# MotherBoardV1.net
KiCad netlist of a schematic drawn in EAGLE
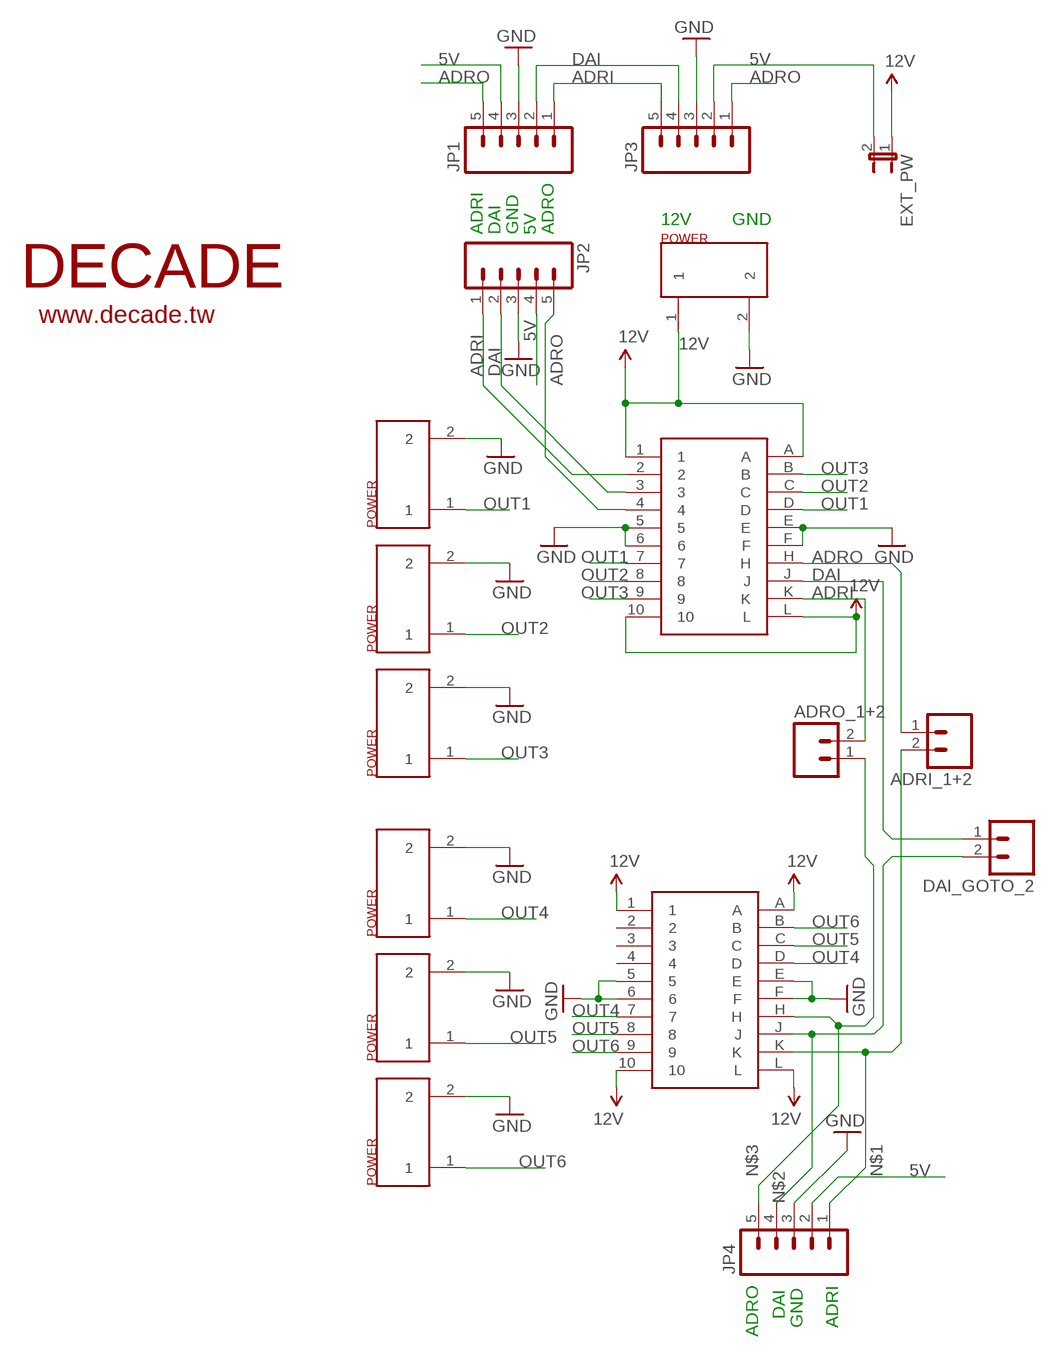
[diagram p0: schematic, sheet 1]

(export (version "E")
  (design (tool "Eeschema 10.0.6"))
  (components
    (comp (ref "ADRI_1+2")
      (value "M02LOCK")
      (footprint "eagle-import:1X02_LOCK")
      (libsource (lib "eagle-import") (part "M02LOCK"))
    )
    (comp (ref "ADRO_1+2")
      (value "M02LOCK")
      (footprint "eagle-import:1X02_LOCK")
      (libsource (lib "eagle-import") (part "M02LOCK"))
    )
    (comp (ref "DAI_GOTO_2")
      (value "M02LOCK")
      (footprint "eagle-import:1X02_LOCK")
      (libsource (lib "eagle-import") (part "M02LOCK"))
    )
    (comp (ref "EXT_PW")
      (value "JUMPER-2SMD-NO")
      (footprint "eagle-import:SJ_2S-NO")
      (libsource (lib "eagle-import") (part "JUMPER-2SMD-NO"))
    )
    (comp (ref "JP1")
      (value "M05SCREW")
      (footprint "eagle-import:SCREWTERMINAL-3.5MM-5")
      (libsource (lib "eagle-import") (part "M05SCREW"))
    )
    (comp (ref "JP2")
      (value "M05SCREW")
      (footprint "eagle-import:SCREWTERMINAL-3.5MM-5")
      (libsource (lib "eagle-import") (part "M05SCREW"))
    )
    (comp (ref "JP3")
      (value "M05SCREW")
      (footprint "eagle-import:SCREWTERMINAL-3.5MM-5")
      (libsource (lib "eagle-import") (part "M05SCREW"))
    )
    (comp (ref "JP4")
      (value "M05SCREW")
      (footprint "eagle-import:SCREWTERMINAL-3.5MM-5")
      (libsource (lib "eagle-import") (part "M05SCREW"))
    )
    (comp (ref "U$1")
      (value "1X02_POWER_9MM")
      (footprint "eagle-import:1X02_9MM_POWER")
      (libsource (lib "eagle-import") (part "1X02_POWER_9MM"))
    )
    (comp (ref "U$2")
      (value "1X02_POWER_9MM")
      (footprint "eagle-import:1X02_9MM_POWER")
      (libsource (lib "eagle-import") (part "1X02_POWER_9MM"))
    )
    (comp (ref "U$3")
      (value "1X02_POWER_9MM")
      (footprint "eagle-import:1X02_9MM_POWER")
      (libsource (lib "eagle-import") (part "1X02_POWER_9MM"))
    )
    (comp (ref "U$4")
      (value "LW-N10A2G")
      (footprint "eagle-import:LW-N10A2G")
      (libsource (lib "eagle-import") (part "LW-N10A2G"))
    )
    (comp (ref "U$5")
      (value "1X02_POWER_9MM")
      (footprint "eagle-import:1X02_9MM_POWER")
      (libsource (lib "eagle-import") (part "1X02_POWER_9MM"))
    )
    (comp (ref "U$6")
      (value "1X02_POWER_9MM")
      (footprint "eagle-import:1X02_9MM_POWER")
      (libsource (lib "eagle-import") (part "1X02_POWER_9MM"))
    )
    (comp (ref "U$7")
      (value "1X02_POWER_9MM")
      (footprint "eagle-import:1X02_9MM_POWER")
      (libsource (lib "eagle-import") (part "1X02_POWER_9MM"))
    )
    (comp (ref "U$8")
      (value "1X02_POWER_9MM")
      (footprint "eagle-import:1X02_9MM_POWER")
      (libsource (lib "eagle-import") (part "1X02_POWER_9MM"))
    )
    (comp (ref "U$9")
      (value "LW-N10A2G")
      (footprint "eagle-import:LW-N10A2G")
      (libsource (lib "eagle-import") (part "LW-N10A2G"))
    )
    (comp (ref "U$11")
      (value "DECADE-LOGO-SMALL")
      (footprint "eagle-import:DECADE-LOGO-SMALL")
      (libsource (lib "eagle-import") (part "DECADE-LOGO-SMALL"))
    )
  )
  (nets
    (net (code "1") (name "/5V") (class "Default")
      (node (ref "EXT_PW") (pin "2") (pinfunction "2_2") (pintype "passive"))
      (node (ref "JP1") (pin "4") (pinfunction "4_4") (pintype "passive"))
      (node (ref "JP2") (pin "4") (pinfunction "4_4") (pintype "passive"))
      (node (ref "JP3") (pin "2") (pinfunction "2_2") (pintype "passive"))
      (node (ref "JP4") (pin "2") (pinfunction "2_2") (pintype "passive"))
    )
    (net (code "2") (name "/ADRI") (class "Default")
      (node (ref "ADRO_1+2") (pin "2") (pinfunction "2_2") (pintype "passive"))
      (node (ref "JP1") (pin "1") (pinfunction "1_1") (pintype "passive"))
      (node (ref "JP2") (pin "1") (pinfunction "1_1") (pintype "passive"))
      (node (ref "JP3") (pin "5") (pinfunction "5_5") (pintype "passive"))
      (node (ref "U$4") (pin "2") (pinfunction "2_2") (pintype "bidirectional"))
      (node (ref "U$4") (pin "K") (pinfunction "K_K") (pintype "bidirectional"))
    )
    (net (code "3") (name "/ADRO") (class "Default")
      (node (ref "ADRI_1+2") (pin "1") (pinfunction "1_1") (pintype "passive"))
      (node (ref "JP1") (pin "5") (pinfunction "5_5") (pintype "passive"))
      (node (ref "JP2") (pin "5") (pinfunction "5_5") (pintype "passive"))
      (node (ref "JP3") (pin "1") (pinfunction "1_1") (pintype "passive"))
      (node (ref "U$4") (pin "4") (pinfunction "4_4") (pintype "bidirectional"))
      (node (ref "U$4") (pin "H") (pinfunction "H_H") (pintype "bidirectional"))
    )
    (net (code "4") (name "/DAI") (class "Default")
      (node (ref "DAI_GOTO_2") (pin "1") (pinfunction "1_1") (pintype "passive"))
      (node (ref "JP1") (pin "2") (pinfunction "2_2") (pintype "passive"))
      (node (ref "JP2") (pin "2") (pinfunction "2_2") (pintype "passive"))
      (node (ref "JP3") (pin "4") (pinfunction "4_4") (pintype "passive"))
      (node (ref "U$4") (pin "3") (pinfunction "3_3") (pintype "bidirectional"))
      (node (ref "U$4") (pin "J") (pinfunction "J_J") (pintype "bidirectional"))
    )
    (net (code "5") (name "/N$1") (class "Default")
      (node (ref "ADRI_1+2") (pin "2") (pinfunction "2_2") (pintype "passive"))
      (node (ref "JP4") (pin "1") (pinfunction "1_1") (pintype "passive"))
      (node (ref "U$9") (pin "K") (pinfunction "K_K") (pintype "bidirectional"))
    )
    (net (code "6") (name "/N$2") (class "Default")
      (node (ref "DAI_GOTO_2") (pin "2") (pinfunction "2_2") (pintype "passive"))
      (node (ref "JP4") (pin "4") (pinfunction "4_4") (pintype "passive"))
      (node (ref "U$9") (pin "J") (pinfunction "J_J") (pintype "bidirectional"))
    )
    (net (code "7") (name "/N$3") (class "Default")
      (node (ref "ADRO_1+2") (pin "1") (pinfunction "1_1") (pintype "passive"))
      (node (ref "JP4") (pin "5") (pinfunction "5_5") (pintype "passive"))
      (node (ref "U$9") (pin "H") (pinfunction "H_H") (pintype "bidirectional"))
    )
    (net (code "8") (name "/OUT1") (class "Default")
      (node (ref "U$1") (pin "1") (pinfunction "1_1") (pintype "bidirectional"))
      (node (ref "U$4") (pin "7") (pinfunction "7_7") (pintype "bidirectional"))
      (node (ref "U$4") (pin "D") (pinfunction "D_D") (pintype "bidirectional"))
    )
    (net (code "9") (name "/OUT2") (class "Default")
      (node (ref "U$2") (pin "1") (pinfunction "1_1") (pintype "bidirectional"))
      (node (ref "U$4") (pin "8") (pinfunction "8_8") (pintype "bidirectional"))
      (node (ref "U$4") (pin "C") (pinfunction "C_C") (pintype "bidirectional"))
    )
    (net (code "10") (name "/OUT3") (class "Default")
      (node (ref "U$3") (pin "1") (pinfunction "1_1") (pintype "bidirectional"))
      (node (ref "U$4") (pin "9") (pinfunction "9_9") (pintype "bidirectional"))
      (node (ref "U$4") (pin "B") (pinfunction "B_B") (pintype "bidirectional"))
    )
    (net (code "11") (name "/OUT4") (class "Default")
      (node (ref "U$6") (pin "1") (pinfunction "1_1") (pintype "bidirectional"))
      (node (ref "U$9") (pin "7") (pinfunction "7_7") (pintype "bidirectional"))
      (node (ref "U$9") (pin "D") (pinfunction "D_D") (pintype "bidirectional"))
    )
    (net (code "12") (name "/OUT5") (class "Default")
      (node (ref "U$7") (pin "1") (pinfunction "1_1") (pintype "bidirectional"))
      (node (ref "U$9") (pin "8") (pinfunction "8_8") (pintype "bidirectional"))
      (node (ref "U$9") (pin "C") (pinfunction "C_C") (pintype "bidirectional"))
    )
    (net (code "13") (name "/OUT6") (class "Default")
      (node (ref "U$8") (pin "1") (pinfunction "1_1") (pintype "bidirectional"))
      (node (ref "U$9") (pin "9") (pinfunction "9_9") (pintype "bidirectional"))
      (node (ref "U$9") (pin "B") (pinfunction "B_B") (pintype "bidirectional"))
    )
    (net (code "14") (name "12V") (class "Default")
      (node (ref "EXT_PW") (pin "1") (pinfunction "1_1") (pintype "passive"))
      (node (ref "U$4") (pin "1") (pinfunction "1_1") (pintype "bidirectional"))
      (node (ref "U$4") (pin "10") (pinfunction "10_10") (pintype "bidirectional"))
      (node (ref "U$4") (pin "A") (pinfunction "A_A") (pintype "bidirectional"))
      (node (ref "U$4") (pin "L") (pinfunction "L_L") (pintype "bidirectional"))
      (node (ref "U$5") (pin "1") (pinfunction "1_1") (pintype "bidirectional"))
      (node (ref "U$9") (pin "1") (pinfunction "1_1") (pintype "bidirectional"))
      (node (ref "U$9") (pin "10") (pinfunction "10_10") (pintype "bidirectional"))
      (node (ref "U$9") (pin "A") (pinfunction "A_A") (pintype "bidirectional"))
      (node (ref "U$9") (pin "L") (pinfunction "L_L") (pintype "bidirectional"))
    )
    (net (code "15") (name "GND") (class "Default")
      (node (ref "JP1") (pin "3") (pinfunction "3_3") (pintype "passive"))
      (node (ref "JP2") (pin "3") (pinfunction "3_3") (pintype "passive"))
      (node (ref "JP3") (pin "3") (pinfunction "3_3") (pintype "passive"))
      (node (ref "JP4") (pin "3") (pinfunction "3_3") (pintype "passive"))
      (node (ref "U$1") (pin "2") (pinfunction "2_2") (pintype "bidirectional"))
      (node (ref "U$2") (pin "2") (pinfunction "2_2") (pintype "bidirectional"))
      (node (ref "U$3") (pin "2") (pinfunction "2_2") (pintype "bidirectional"))
      (node (ref "U$4") (pin "5") (pinfunction "5_5") (pintype "bidirectional"))
      (node (ref "U$4") (pin "6") (pinfunction "6_6") (pintype "bidirectional"))
      (node (ref "U$4") (pin "E") (pinfunction "E_E") (pintype "bidirectional"))
      (node (ref "U$4") (pin "F") (pinfunction "F_F") (pintype "bidirectional"))
      (node (ref "U$5") (pin "2") (pinfunction "2_2") (pintype "bidirectional"))
      (node (ref "U$6") (pin "2") (pinfunction "2_2") (pintype "bidirectional"))
      (node (ref "U$7") (pin "2") (pinfunction "2_2") (pintype "bidirectional"))
      (node (ref "U$8") (pin "2") (pinfunction "2_2") (pintype "bidirectional"))
      (node (ref "U$9") (pin "5") (pinfunction "5_5") (pintype "bidirectional"))
      (node (ref "U$9") (pin "6") (pinfunction "6_6") (pintype "bidirectional"))
      (node (ref "U$9") (pin "E") (pinfunction "E_E") (pintype "bidirectional"))
      (node (ref "U$9") (pin "F") (pinfunction "F_F") (pintype "bidirectional"))
    )
    (net (code "16") (name "unconnected-(U$9-Pad2)") (class "Default")
      (node (ref "U$9") (pin "2") (pinfunction "2_2") (pintype "bidirectional"))
    )
    (net (code "17") (name "unconnected-(U$9-Pad3)") (class "Default")
      (node (ref "U$9") (pin "3") (pinfunction "3_3") (pintype "bidirectional"))
    )
    (net (code "18") (name "unconnected-(U$9-Pad4)") (class "Default")
      (node (ref "U$9") (pin "4") (pinfunction "4_4") (pintype "bidirectional"))
    )
  )
)
